# TheLittleEngineers_org-2732-TOFROM-2532-.net
KiCad netlist of a schematic drawn in EAGLE
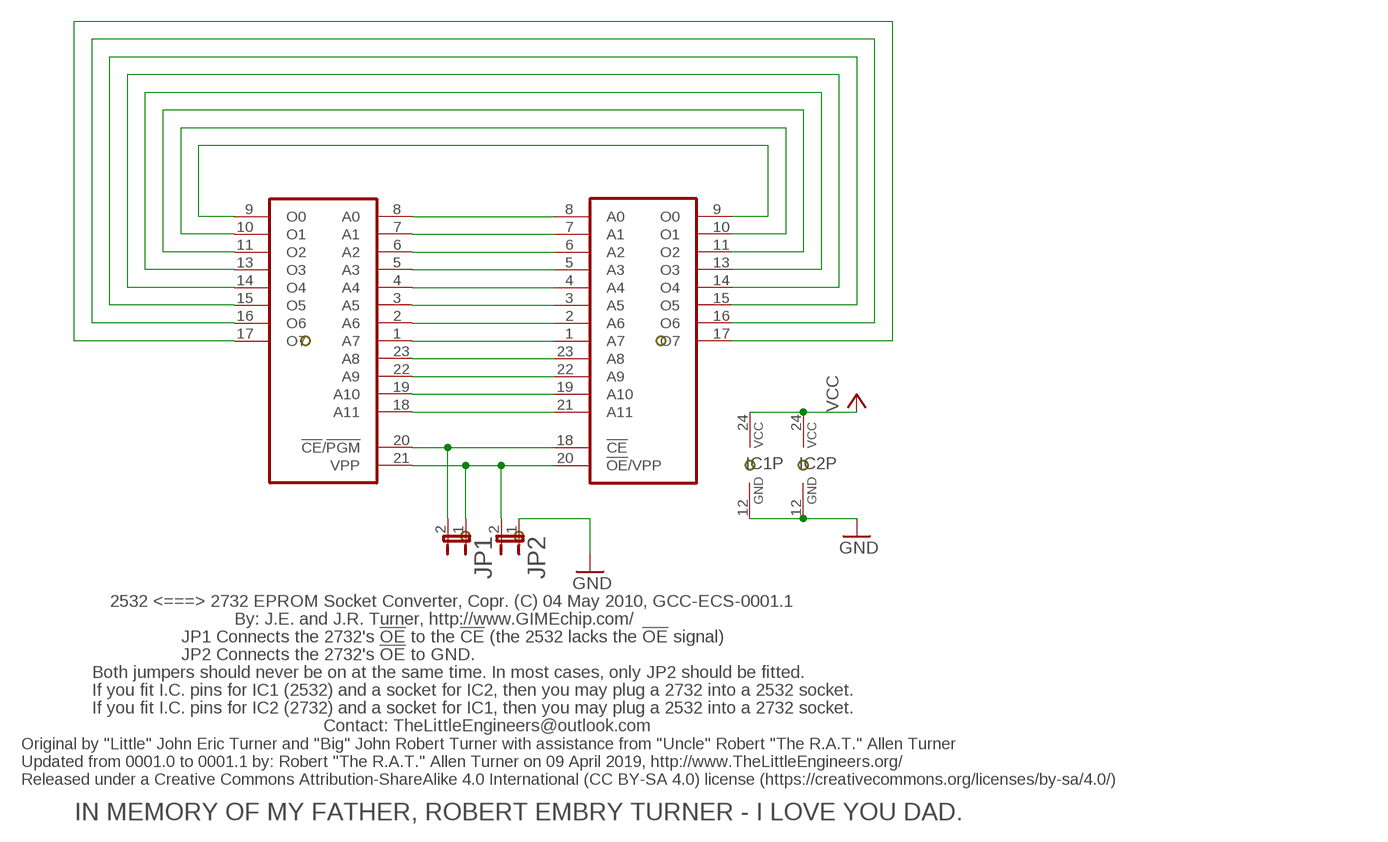
[diagram p0: schematic, sheet 1]

(export (version "E")
  (design (tool "Eeschema 10.0.6"))
  (components
    (comp (ref "IC1")
      (value "2532")
      (footprint "eagle-import:DIL24")
      (libsource (lib "eagle-import") (part "2532"))
    )
    (comp (ref "IC2")
      (value "2732")
      (footprint "eagle-import:DIL24")
      (libsource (lib "eagle-import") (part "2732"))
    )
    (comp (ref "JP1")
      (value "JP")
      (footprint "eagle-import:JP1")
      (libsource (lib "eagle-import") (part "JP"))
    )
    (comp (ref "JP2")
      (value "JP")
      (footprint "eagle-import:JP1")
      (libsource (lib "eagle-import") (part "JP"))
    )
  )
  (nets
    (net (code "1") (name "GND") (class "Default")
      (node (ref "IC1") (pin "12") (pinfunction "GND_12") (pintype "power_in"))
      (node (ref "IC2") (pin "12") (pinfunction "GND_12") (pintype "power_in"))
      (node (ref "JP2") (pin "1") (pinfunction "1_1") (pintype "passive"))
    )
    (net (code "2") (name "Net-(IC1A-A0)") (class "Default")
      (node (ref "IC1") (pin "8") (pinfunction "A0_8") (pintype "input"))
      (node (ref "IC2") (pin "8") (pinfunction "A0_8") (pintype "input"))
    )
    (net (code "3") (name "Net-(IC1A-A1)") (class "Default")
      (node (ref "IC1") (pin "7") (pinfunction "A1_7") (pintype "input"))
      (node (ref "IC2") (pin "7") (pinfunction "A1_7") (pintype "input"))
    )
    (net (code "4") (name "Net-(IC1A-A2)") (class "Default")
      (node (ref "IC1") (pin "6") (pinfunction "A2_6") (pintype "input"))
      (node (ref "IC2") (pin "6") (pinfunction "A2_6") (pintype "input"))
    )
    (net (code "5") (name "Net-(IC1A-A3)") (class "Default")
      (node (ref "IC1") (pin "5") (pinfunction "A3_5") (pintype "input"))
      (node (ref "IC2") (pin "5") (pinfunction "A3_5") (pintype "input"))
    )
    (net (code "6") (name "Net-(IC1A-A4)") (class "Default")
      (node (ref "IC1") (pin "4") (pinfunction "A4_4") (pintype "input"))
      (node (ref "IC2") (pin "4") (pinfunction "A4_4") (pintype "input"))
    )
    (net (code "7") (name "Net-(IC1A-A5)") (class "Default")
      (node (ref "IC1") (pin "3") (pinfunction "A5_3") (pintype "input"))
      (node (ref "IC2") (pin "3") (pinfunction "A5_3") (pintype "input"))
    )
    (net (code "8") (name "Net-(IC1A-A6)") (class "Default")
      (node (ref "IC1") (pin "2") (pinfunction "A6_2") (pintype "input"))
      (node (ref "IC2") (pin "2") (pinfunction "A6_2") (pintype "input"))
    )
    (net (code "9") (name "Net-(IC1A-A7)") (class "Default")
      (node (ref "IC1") (pin "1") (pinfunction "A7_1") (pintype "input"))
      (node (ref "IC2") (pin "1") (pinfunction "A7_1") (pintype "input"))
    )
    (net (code "10") (name "Net-(IC1A-A8)") (class "Default")
      (node (ref "IC1") (pin "23") (pinfunction "A8_23") (pintype "input"))
      (node (ref "IC2") (pin "23") (pinfunction "A8_23") (pintype "input"))
    )
    (net (code "11") (name "Net-(IC1A-A9)") (class "Default")
      (node (ref "IC1") (pin "22") (pinfunction "A9_22") (pintype "input"))
      (node (ref "IC2") (pin "22") (pinfunction "A9_22") (pintype "input"))
    )
    (net (code "12") (name "Net-(IC1A-A10)") (class "Default")
      (node (ref "IC1") (pin "19") (pinfunction "A10_19") (pintype "input"))
      (node (ref "IC2") (pin "19") (pinfunction "A10_19") (pintype "input"))
    )
    (net (code "13") (name "Net-(IC1A-A11)") (class "Default")
      (node (ref "IC1") (pin "18") (pinfunction "A11_18") (pintype "input"))
      (node (ref "IC2") (pin "21") (pinfunction "A11_21") (pintype "input"))
    )
    (net (code "14") (name "Net-(IC1A-O0)") (class "Default")
      (node (ref "IC1") (pin "9") (pinfunction "O0_9") (pintype "tri_state"))
      (node (ref "IC2") (pin "9") (pinfunction "O0_9") (pintype "tri_state"))
    )
    (net (code "15") (name "Net-(IC1A-O1)") (class "Default")
      (node (ref "IC1") (pin "10") (pinfunction "O1_10") (pintype "tri_state"))
      (node (ref "IC2") (pin "10") (pinfunction "O1_10") (pintype "tri_state"))
    )
    (net (code "16") (name "Net-(IC1A-O2)") (class "Default")
      (node (ref "IC1") (pin "11") (pinfunction "O2_11") (pintype "tri_state"))
      (node (ref "IC2") (pin "11") (pinfunction "O2_11") (pintype "tri_state"))
    )
    (net (code "17") (name "Net-(IC1A-O3)") (class "Default")
      (node (ref "IC1") (pin "13") (pinfunction "O3_13") (pintype "tri_state"))
      (node (ref "IC2") (pin "13") (pinfunction "O3_13") (pintype "tri_state"))
    )
    (net (code "18") (name "Net-(IC1A-O4)") (class "Default")
      (node (ref "IC1") (pin "14") (pinfunction "O4_14") (pintype "tri_state"))
      (node (ref "IC2") (pin "14") (pinfunction "O4_14") (pintype "tri_state"))
    )
    (net (code "19") (name "Net-(IC1A-O5)") (class "Default")
      (node (ref "IC1") (pin "15") (pinfunction "O5_15") (pintype "tri_state"))
      (node (ref "IC2") (pin "15") (pinfunction "O5_15") (pintype "tri_state"))
    )
    (net (code "20") (name "Net-(IC1A-O6)") (class "Default")
      (node (ref "IC1") (pin "16") (pinfunction "O6_16") (pintype "tri_state"))
      (node (ref "IC2") (pin "16") (pinfunction "O6_16") (pintype "tri_state"))
    )
    (net (code "21") (name "Net-(IC1A-O7)") (class "Default")
      (node (ref "IC1") (pin "17") (pinfunction "O7_17") (pintype "tri_state"))
      (node (ref "IC2") (pin "17") (pinfunction "O7_17") (pintype "tri_state"))
    )
    (net (code "22") (name "Net-(IC1A-VPP)") (class "Default")
      (node (ref "IC1") (pin "21") (pinfunction "VPP_21") (pintype "input"))
      (node (ref "IC2") (pin "20") (pinfunction "~{OE}/VPP_20") (pintype "input"))
      (node (ref "JP1") (pin "1") (pinfunction "1_1") (pintype "passive"))
      (node (ref "JP2") (pin "2") (pinfunction "2_2") (pintype "passive"))
    )
    (net (code "23") (name "Net-(IC1A-~{CE}{slash}~{PGM})") (class "Default")
      (node (ref "IC1") (pin "20") (pinfunction "~{CE}/~{PGM}_20") (pintype "input"))
      (node (ref "IC2") (pin "18") (pinfunction "~{CE}_18") (pintype "input"))
      (node (ref "JP1") (pin "2") (pinfunction "2_2") (pintype "passive"))
    )
    (net (code "24") (name "VCC") (class "Default")
      (node (ref "IC1") (pin "24") (pinfunction "VCC_24") (pintype "power_in"))
      (node (ref "IC2") (pin "24") (pinfunction "VCC_24") (pintype "power_in"))
    )
  )
)
